# ID-Serial.net
KiCad netlist of a schematic drawn in Altium Designer
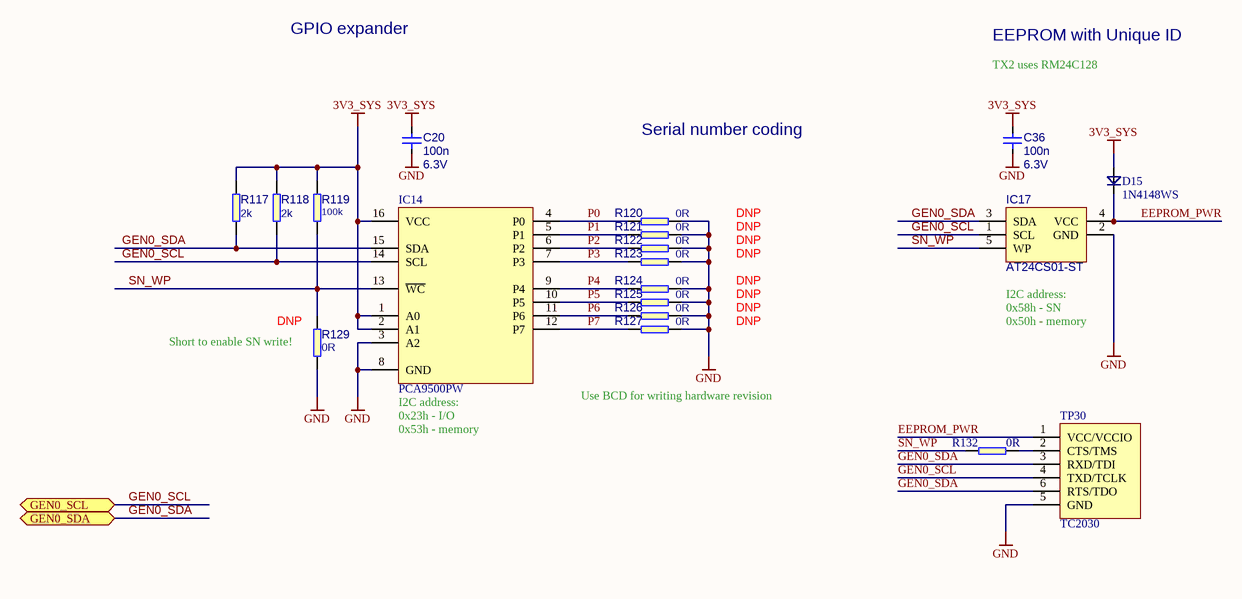
[diagram p0: ID-Serial.SchDoc]

(export (version "E")
  (design (tool "Eeschema 10.0.6"))
  (components
    (comp (ref "C20")
      (value "100n")
      (footprint "0402")
      (description "MLCC SMT Capacitor 100n 0402")
      (fields
        (field (name "MANUFACTURER") "TDK")
        (field (name "PARTNUMBER") "C_100n_0402")
        (field (name "VOLTAGE") "6.3V")
      )
      (libsource (lib "jetson-nano-baseboard") (part "C_100n_0402"))
    )
    (comp (ref "C36")
      (value "100n")
      (footprint "0402")
      (description "MLCC SMT Capacitor 100n 0402")
      (fields
        (field (name "MANUFACTURER") "TDK")
        (field (name "PARTNUMBER") "C_100n_0402")
        (field (name "VOLTAGE") "6.3V")
      )
      (libsource (lib "jetson-nano-baseboard") (part "C_100n_0402"))
    )
    (comp (ref "D15")
      (value "1N4148WS")
      (footprint "SOD-323")
      (description "Diode small signal")
      (fields (field (name "MANUFACTURER") "ON SEMICONDUCTOR"))
      (libsource (lib "jetson-nano-baseboard") (part "diode"))
    )
    (comp (ref "IC14")
      (value "PCA9500PW")
      (footprint "TSSOP-16")
      (description "Remote 8bit I2C SMBus I/O expander w/ 2kbit EEPROM memory")
      (fields (field (name "MANUFACTURER") "NXP Semicondutors"))
      (libsource (lib "jetson-nano-baseboard") (part "PCA9500PW"))
    )
    (comp (ref "IC17")
      (value "AT24CS01-ST")
      (footprint "SOT23-5")
      (fields (field (name "MANUFACTURER") "Atmel"))
      (libsource (lib "jetson-nano-baseboard") (part "AT24CS01"))
    )
    (comp (ref "R117")
      (value "2k")
      (footprint "0402")
      (description "RES, 2k, 0402")
      (fields (field (name "PARTNUMBER") "R_2k_0402") (field (name "MANUFACTURER") "VISHAY"))
      (libsource (lib "jetson-nano-baseboard") (part "R_2k_0402"))
    )
    (comp (ref "R118")
      (value "2k")
      (footprint "0402")
      (description "RES, 2k, 0402")
      (fields (field (name "PARTNUMBER") "R_2k_0402") (field (name "MANUFACTURER") "VISHAY"))
      (libsource (lib "jetson-nano-baseboard") (part "R_2k_0402"))
    )
    (comp (ref "R119")
      (value "100k")
      (footprint "0402")
      (description "SMT Resistor 100k 0402")
      (fields (field (name "PARTNUMBER") "R_100k_0402") (field (name "TOLERANCE") "1%"))
      (libsource (lib "jetson-nano-baseboard") (part "R_100k_0402"))
    )
    (comp (ref "R120")
      (value "0R")
      (footprint "0402")
      (description "RES, 0R, 0402")
      (fields (field (name "PARTNUMBER") "R_0R_0402") (field (name "MANUFACTURER") "Panasonic"))
      (libsource (lib "jetson-nano-baseboard") (part "R_0R_0402"))
    )
    (comp (ref "R121")
      (value "0R")
      (footprint "0402")
      (description "RES, 0R, 0402")
      (fields (field (name "PARTNUMBER") "R_0R_0402") (field (name "MANUFACTURER") "Panasonic"))
      (libsource (lib "jetson-nano-baseboard") (part "R_0R_0402"))
    )
    (comp (ref "R122")
      (value "0R")
      (footprint "0402")
      (description "RES, 0R, 0402")
      (fields (field (name "PARTNUMBER") "R_0R_0402") (field (name "MANUFACTURER") "Panasonic"))
      (libsource (lib "jetson-nano-baseboard") (part "R_0R_0402"))
    )
    (comp (ref "R123")
      (value "0R")
      (footprint "0402")
      (description "RES, 0R, 0402")
      (fields (field (name "PARTNUMBER") "R_0R_0402") (field (name "MANUFACTURER") "Panasonic"))
      (libsource (lib "jetson-nano-baseboard") (part "R_0R_0402"))
    )
    (comp (ref "R124")
      (value "0R")
      (footprint "0402")
      (description "RES, 0R, 0402")
      (fields (field (name "PARTNUMBER") "R_0R_0402") (field (name "MANUFACTURER") "Panasonic"))
      (libsource (lib "jetson-nano-baseboard") (part "R_0R_0402"))
    )
    (comp (ref "R125")
      (value "0R")
      (footprint "0402")
      (description "RES, 0R, 0402")
      (fields (field (name "PARTNUMBER") "R_0R_0402") (field (name "MANUFACTURER") "Panasonic"))
      (libsource (lib "jetson-nano-baseboard") (part "R_0R_0402"))
    )
    (comp (ref "R126")
      (value "0R")
      (footprint "0402")
      (description "RES, 0R, 0402")
      (fields (field (name "PARTNUMBER") "R_0R_0402") (field (name "MANUFACTURER") "Panasonic"))
      (libsource (lib "jetson-nano-baseboard") (part "R_0R_0402"))
    )
    (comp (ref "R127")
      (value "0R")
      (footprint "0402")
      (description "RES, 0R, 0402")
      (fields (field (name "PARTNUMBER") "R_0R_0402") (field (name "MANUFACTURER") "Panasonic"))
      (libsource (lib "jetson-nano-baseboard") (part "R_0R_0402"))
    )
    (comp (ref "R129")
      (value "0R")
      (footprint "0402")
      (description "RES, 0R, 0402")
      (fields (field (name "PARTNUMBER") "R_0R_0402") (field (name "MANUFACTURER") "Panasonic"))
      (libsource (lib "") (part "R_0R_0402_1"))
    )
    (comp (ref "R132")
      (value "0R")
      (footprint "0402")
      (description "RES, 0R, 0402")
      (fields (field (name "PARTNUMBER") "R_0R_0402") (field (name "MANUFACTURER") "Panasonic"))
      (libsource (lib "jetson-nano-baseboard") (part "R_0R_0402"))
    )
    (comp (ref "TP30")
      (value "TC2030")
      (footprint "TC2030")
      (fields (field (name "MANUFACTURER") "Tag-Connect"))
      (libsource (lib "jetson-nano-baseboard") (part "TC2030"))
    )
  )
  (nets
    (net (code "1") (name "/EEPROM_PWR") (class "Default")
      (node (ref "D15") (pin "C") (pinfunction "C_C") (pintype "passive"))
      (node (ref "IC17") (pin "4") (pinfunction "VCC_4") (pintype "passive"))
      (node (ref "TP30") (pin "1") (pinfunction "VCC/VCCIO_1") (pintype "passive"))
    )
    (net (code "2") (name "/GEN0_SCL") (class "Default")
      (node (ref "IC14") (pin "14") (pinfunction "SCL_14") (pintype "passive"))
      (node (ref "IC17") (pin "1") (pinfunction "SCL_1") (pintype "passive"))
      (node (ref "R118") (pin "2") (pintype "passive"))
      (node (ref "TP30") (pin "4") (pinfunction "TXD/TCLK_4") (pintype "passive"))
    )
    (net (code "3") (name "/GEN0_SDA") (class "Default")
      (node (ref "IC14") (pin "15") (pinfunction "SDA_15") (pintype "passive"))
      (node (ref "IC17") (pin "3") (pinfunction "SDA_3") (pintype "passive"))
      (node (ref "R117") (pin "2") (pintype "passive"))
      (node (ref "TP30") (pin "3") (pinfunction "RXD/TDI_3") (pintype "passive"))
      (node (ref "TP30") (pin "6") (pinfunction "RTS/TDO_6") (pintype "passive"))
    )
    (net (code "4") (name "/P0") (class "Default")
      (node (ref "IC14") (pin "4") (pinfunction "P0_4") (pintype "passive"))
      (node (ref "R120") (pin "1") (pintype "passive"))
    )
    (net (code "5") (name "/P1") (class "Default")
      (node (ref "IC14") (pin "5") (pinfunction "P1_5") (pintype "passive"))
      (node (ref "R121") (pin "1") (pintype "passive"))
    )
    (net (code "6") (name "/P2") (class "Default")
      (node (ref "IC14") (pin "6") (pinfunction "P2_6") (pintype "passive"))
      (node (ref "R122") (pin "1") (pintype "passive"))
    )
    (net (code "7") (name "/P3") (class "Default")
      (node (ref "IC14") (pin "7") (pinfunction "P3_7") (pintype "passive"))
      (node (ref "R123") (pin "1") (pintype "passive"))
    )
    (net (code "8") (name "/P4") (class "Default")
      (node (ref "IC14") (pin "9") (pinfunction "P4_9") (pintype "passive"))
      (node (ref "R124") (pin "1") (pintype "passive"))
    )
    (net (code "9") (name "/P5") (class "Default")
      (node (ref "IC14") (pin "10") (pinfunction "P5_10") (pintype "passive"))
      (node (ref "R125") (pin "1") (pintype "passive"))
    )
    (net (code "10") (name "/P6") (class "Default")
      (node (ref "IC14") (pin "11") (pinfunction "P6_11") (pintype "passive"))
      (node (ref "R126") (pin "1") (pintype "passive"))
    )
    (net (code "11") (name "/P7") (class "Default")
      (node (ref "IC14") (pin "12") (pinfunction "P7_12") (pintype "passive"))
      (node (ref "R127") (pin "1") (pintype "passive"))
    )
    (net (code "12") (name "/SN_WP") (class "Default")
      (node (ref "IC14") (pin "13") (pinfunction "~{WC}_13") (pintype "passive"))
      (node (ref "IC17") (pin "5") (pinfunction "WP_5") (pintype "passive"))
      (node (ref "R119") (pin "2") (pintype "passive"))
      (node (ref "R129") (pin "2") (pintype "passive"))
      (node (ref "R132") (pin "1") (pintype "passive"))
    )
    (net (code "13") (name "3V3_SYS") (class "Default")
      (node (ref "C20") (pin "2") (pinfunction "2_2") (pintype "passive"))
      (node (ref "C36") (pin "2") (pinfunction "2_2") (pintype "passive"))
      (node (ref "D15") (pin "A") (pinfunction "A_A") (pintype "passive"))
      (node (ref "IC14") (pin "1") (pinfunction "A0_1") (pintype "passive"))
      (node (ref "IC14") (pin "16") (pinfunction "VCC_16") (pintype "passive"))
      (node (ref "IC14") (pin "2") (pinfunction "A1_2") (pintype "passive"))
      (node (ref "R117") (pin "1") (pintype "passive"))
      (node (ref "R118") (pin "1") (pintype "passive"))
      (node (ref "R119") (pin "1") (pintype "passive"))
    )
    (net (code "14") (name "GND") (class "Default")
      (node (ref "C20") (pin "1") (pinfunction "1_1") (pintype "passive"))
      (node (ref "C36") (pin "1") (pinfunction "1_1") (pintype "passive"))
      (node (ref "IC14") (pin "3") (pinfunction "A2_3") (pintype "passive"))
      (node (ref "IC14") (pin "8") (pinfunction "GND_8") (pintype "passive"))
      (node (ref "IC17") (pin "2") (pinfunction "GND_2") (pintype "passive"))
      (node (ref "R120") (pin "2") (pintype "passive"))
      (node (ref "R121") (pin "2") (pintype "passive"))
      (node (ref "R122") (pin "2") (pintype "passive"))
      (node (ref "R123") (pin "2") (pintype "passive"))
      (node (ref "R124") (pin "2") (pintype "passive"))
      (node (ref "R125") (pin "2") (pintype "passive"))
      (node (ref "R126") (pin "2") (pintype "passive"))
      (node (ref "R127") (pin "2") (pintype "passive"))
      (node (ref "R129") (pin "1") (pintype "passive"))
      (node (ref "TP30") (pin "5") (pinfunction "GND_5") (pintype "passive"))
    )
    (net (code "15") (name "Net-(TP30-CTS{slash}TMS)") (class "Default")
      (node (ref "R132") (pin "2") (pintype "passive"))
      (node (ref "TP30") (pin "2") (pinfunction "CTS/TMS_2") (pintype "passive"))
    )
  )
)
